# line_kick.net
KiCad netlist of a schematic drawn in EAGLE
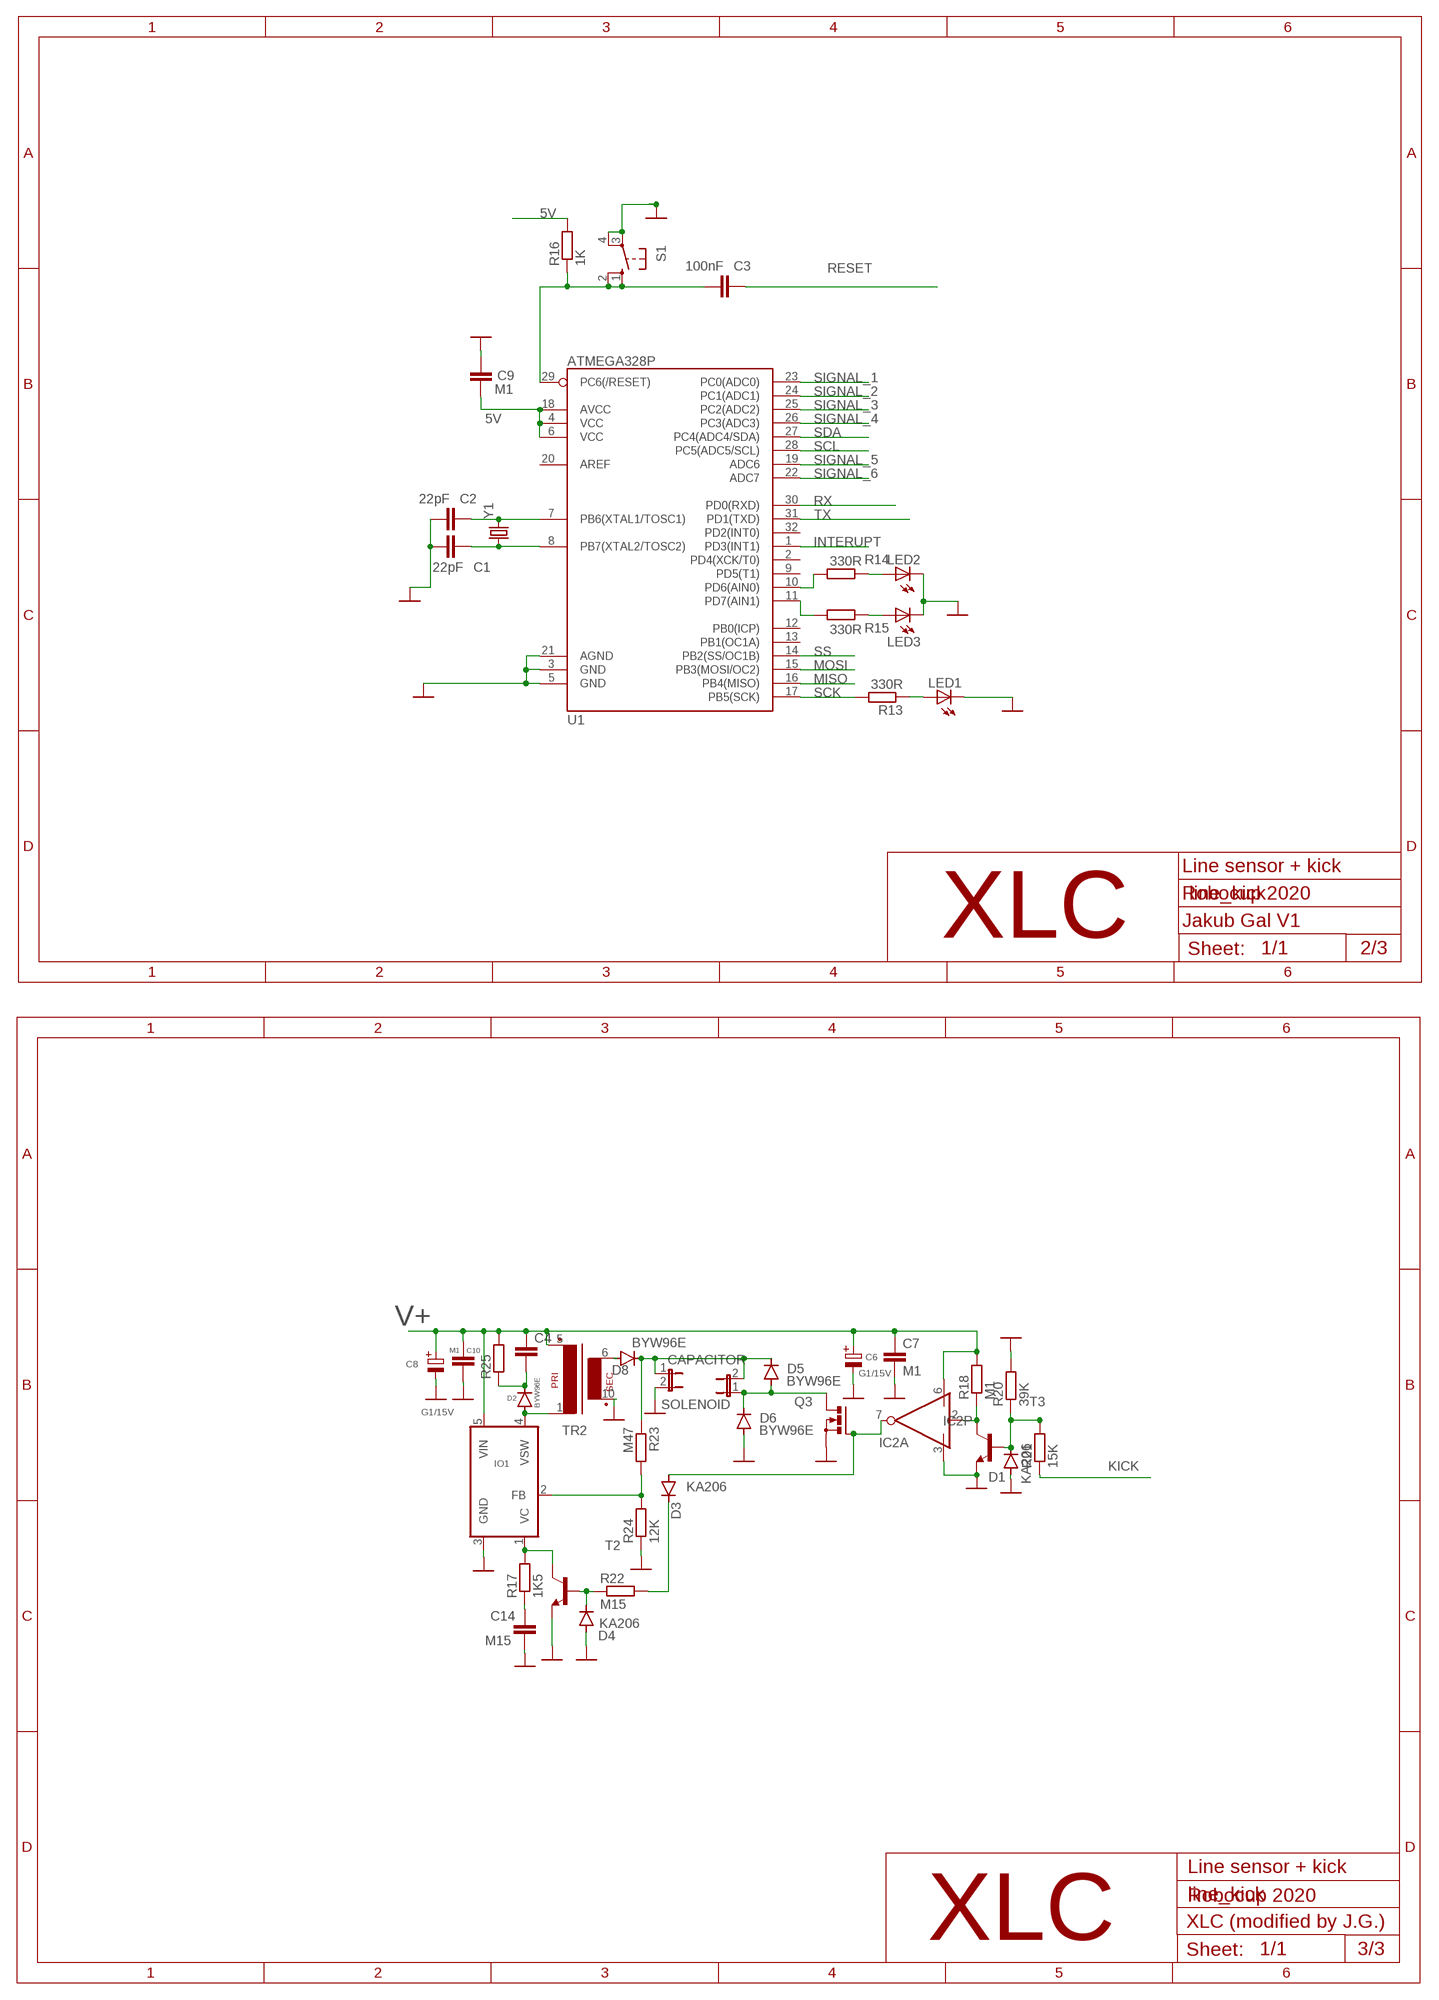
[diagram p0: schematic, sheet 1, part 1 of 2]
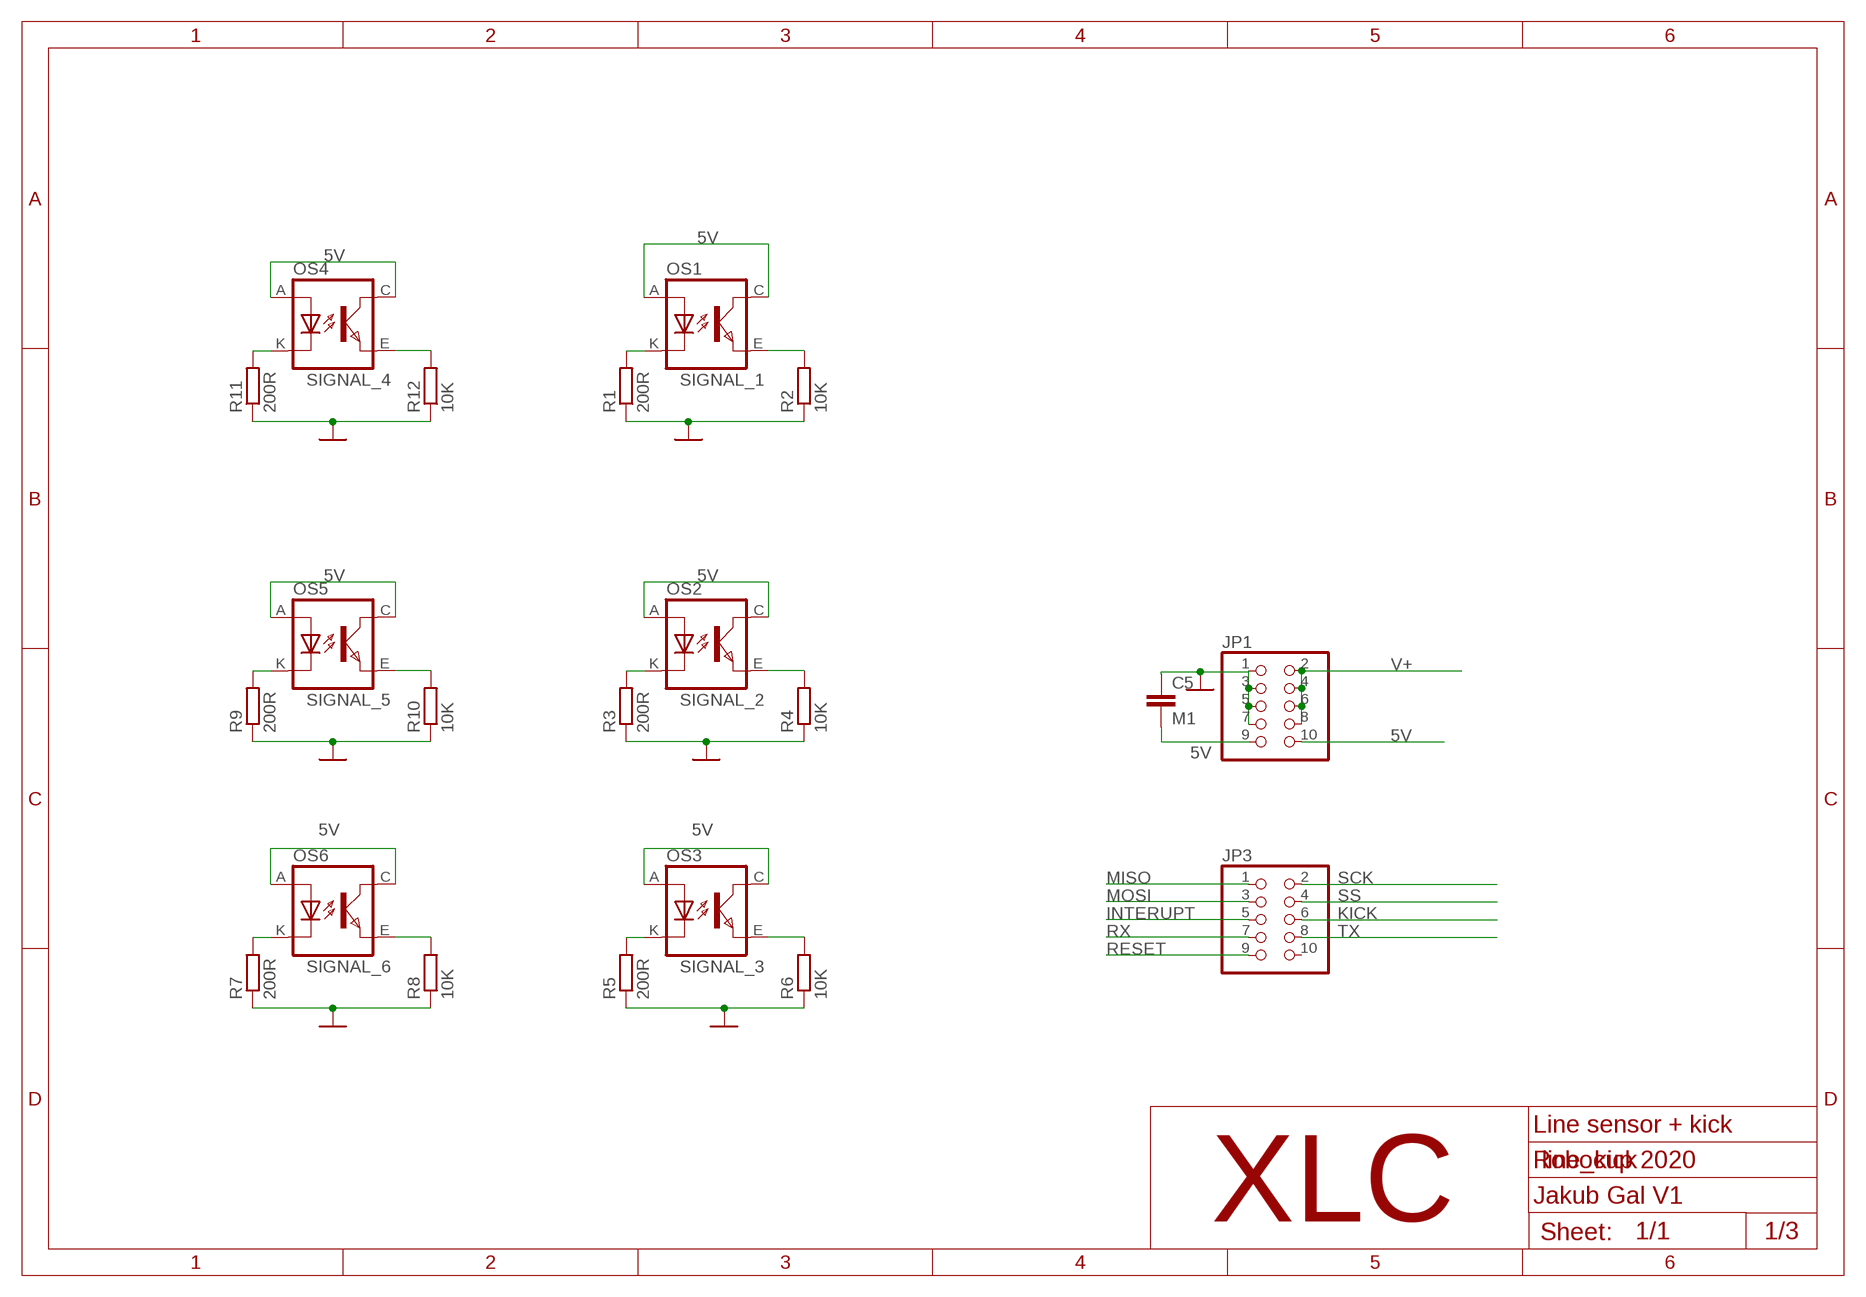
[diagram p1: schematic, sheet 1, part 2 of 2]

(export (version "E")
  (design (tool "Eeschema 10.0.6"))
  (components
    (comp (ref "C1")
      (value "22pF")
      (footprint "eagle-import:C0603")
      (libsource (lib "eagle-import") (part "C-EUC0603"))
    )
    (comp (ref "C2")
      (value "22pF")
      (footprint "eagle-import:C0603")
      (libsource (lib "eagle-import") (part "C-EUC0603"))
    )
    (comp (ref "C3")
      (value "100nF")
      (footprint "eagle-import:C0603")
      (libsource (lib "eagle-import") (part "C-EUC0603"))
    )
    (comp (ref "C4")
      (value "C-EU075-052X106")
      (footprint "eagle-import:C075-052X106")
      (libsource (lib "eagle-import") (part "rcl_334_C-EU075-052X106"))
    )
    (comp (ref "C5")
      (value "M1")
      (footprint "eagle-import:C0603")
      (libsource (lib "eagle-import") (part "rcl_334_C-EUC0603"))
    )
    (comp (ref "C6")
      (value "G1/15V")
      (footprint "eagle-import:E-2,5_7-RAD")
      (libsource (lib "eagle-import") (part "KOND-ELEKT-2,5/7"))
    )
    (comp (ref "C7")
      (value "M1")
      (footprint "eagle-import:C0805K")
      (libsource (lib "eagle-import") (part "resistor_348_C-EUC0805K"))
    )
    (comp (ref "C8")
      (value "G1/15V")
      (footprint "eagle-import:E-2,5_7-RAD")
      (libsource (lib "eagle-import") (part "KOND-ELEKT-2,5/7"))
    )
    (comp (ref "C9")
      (value "M1")
      (footprint "eagle-import:C0603")
      (libsource (lib "eagle-import") (part "C-EUC0603"))
    )
    (comp (ref "C10")
      (value "M1")
      (footprint "eagle-import:C0805K")
      (libsource (lib "eagle-import") (part "resistor_348_C-EUC0805K"))
    )
    (comp (ref "C14")
      (value "M15")
      (footprint "eagle-import:C1206")
      (libsource (lib "eagle-import") (part "resistor_348_C-EUC1206"))
    )
    (comp (ref "CAPACITOR")
      (value "JP1E")
      (footprint "eagle-import:JP1")
      (libsource (lib "eagle-import") (part "JP1E"))
    )
    (comp (ref "D1")
      (value "KA206")
      (footprint "eagle-import:D-7.5")
      (libsource (lib "eagle-import") (part "DIODE-D-7.5"))
    )
    (comp (ref "D2")
      (value "BYW96E")
      (footprint "eagle-import:SOD64-10")
      (libsource (lib "eagle-import") (part "BYW96"))
    )
    (comp (ref "D3")
      (value "KA206")
      (footprint "eagle-import:D-7.5")
      (libsource (lib "eagle-import") (part "DIODE-D-7.5"))
    )
    (comp (ref "D4")
      (value "KA206")
      (footprint "eagle-import:D-7.5")
      (libsource (lib "eagle-import") (part "DIODE-D-7.5"))
    )
    (comp (ref "D5")
      (value "BYW96E")
      (footprint "eagle-import:SOD64-10")
      (libsource (lib "eagle-import") (part "BYW96"))
    )
    (comp (ref "D6")
      (value "BYW96E")
      (footprint "eagle-import:SOD64-10")
      (libsource (lib "eagle-import") (part "BYW96"))
    )
    (comp (ref "D8")
      (value "BYW96E")
      (footprint "eagle-import:SOD64-10")
      (libsource (lib "eagle-import") (part "BYW96"))
    )
    (comp (ref "IC2")
      (value "MIC4423BM")
      (footprint "eagle-import:SO08")
      (libsource (lib "eagle-import") (part "MIC4423BM"))
    )
    (comp (ref "IO1")
      (value "LT1071V")
      (footprint "eagle-import:TO220-5P")
      (libsource (lib "eagle-import") (part "LT1071V"))
    )
    (comp (ref "JP1")
      (value "PINHD-2X5IDC")
      (footprint "eagle-import:2X05_IDC")
      (libsource (lib "eagle-import") (part "PINHD-2X5IDC"))
    )
    (comp (ref "JP3")
      (value "PINHD-2X5IDC")
      (footprint "eagle-import:2X05_IDC")
      (libsource (lib "eagle-import") (part "PINHD-2X5IDC"))
    )
    (comp (ref "LED1")
      (value "LEDCHIPLED_0603")
      (footprint "eagle-import:CHIPLED_0603")
      (libsource (lib "eagle-import") (part "LEDCHIPLED_0603"))
    )
    (comp (ref "LED2")
      (value "LEDCHIPLED_0603")
      (footprint "eagle-import:CHIPLED_0603")
      (libsource (lib "eagle-import") (part "LEDCHIPLED_0603"))
    )
    (comp (ref "LED3")
      (value "LEDCHIPLED_0603")
      (footprint "eagle-import:CHIPLED_0603")
      (libsource (lib "eagle-import") (part "LEDCHIPLED_0603"))
    )
    (comp (ref "OS1")
      (value "TCRT5000")
      (footprint "eagle-import:TCRT5000")
      (libsource (lib "eagle-import") (part "TCRT5000"))
    )
    (comp (ref "OS2")
      (value "TCRT5000")
      (footprint "eagle-import:TCRT5000")
      (libsource (lib "eagle-import") (part "TCRT5000"))
    )
    (comp (ref "OS3")
      (value "TCRT5000")
      (footprint "eagle-import:TCRT5000")
      (libsource (lib "eagle-import") (part "TCRT5000"))
    )
    (comp (ref "OS4")
      (value "TCRT5000")
      (footprint "eagle-import:TCRT5000")
      (fields (field (name "SPICEPREFIX") "O"))
      (libsource (lib "eagle-import") (part "TCRT5000"))
    )
    (comp (ref "OS5")
      (value "TCRT5000")
      (footprint "eagle-import:TCRT5000")
      (libsource (lib "eagle-import") (part "TCRT5000"))
    )
    (comp (ref "OS6")
      (value "TCRT5000")
      (footprint "eagle-import:TCRT5000")
      (fields (field (name "SPICEPREFIX") "O"))
      (libsource (lib "eagle-import") (part "TCRT5000"))
    )
    (comp (ref "Q3")
      (value "PMOSFET_NTO220BV")
      (footprint "eagle-import:TO220BV")
      (libsource (lib "eagle-import") (part "PMOSFET_NTO220BV"))
    )
    (comp (ref "R1")
      (value "200R")
      (footprint "eagle-import:R0603")
      (libsource (lib "eagle-import") (part "R-EU_R0603"))
    )
    (comp (ref "R2")
      (value "10K")
      (footprint "eagle-import:R0603")
      (libsource (lib "eagle-import") (part "R-EU_R0603"))
    )
    (comp (ref "R3")
      (value "200R")
      (footprint "eagle-import:R0603")
      (libsource (lib "eagle-import") (part "R-EU_R0603"))
    )
    (comp (ref "R4")
      (value "10K")
      (footprint "eagle-import:R0603")
      (libsource (lib "eagle-import") (part "R-EU_R0603"))
    )
    (comp (ref "R5")
      (value "200R")
      (footprint "eagle-import:R0603")
      (libsource (lib "eagle-import") (part "R-EU_R0603"))
    )
    (comp (ref "R6")
      (value "10K")
      (footprint "eagle-import:R0603")
      (libsource (lib "eagle-import") (part "R-EU_R0603"))
    )
    (comp (ref "R7")
      (value "200R")
      (footprint "eagle-import:R0603")
      (libsource (lib "eagle-import") (part "R-EU_R0603"))
    )
    (comp (ref "R8")
      (value "10K")
      (footprint "eagle-import:R0603")
      (libsource (lib "eagle-import") (part "R-EU_R0603"))
    )
    (comp (ref "R9")
      (value "200R")
      (footprint "eagle-import:R0603")
      (libsource (lib "eagle-import") (part "R-EU_R0603"))
    )
    (comp (ref "R10")
      (value "10K")
      (footprint "eagle-import:R0603")
      (libsource (lib "eagle-import") (part "R-EU_R0603"))
    )
    (comp (ref "R11")
      (value "200R")
      (footprint "eagle-import:R0603")
      (libsource (lib "eagle-import") (part "R-EU_R0603"))
    )
    (comp (ref "R12")
      (value "10K")
      (footprint "eagle-import:R0603")
      (libsource (lib "eagle-import") (part "R-EU_R0603"))
    )
    (comp (ref "R13")
      (value "330R")
      (footprint "eagle-import:R0603")
      (libsource (lib "eagle-import") (part "R-EU_R0603"))
    )
    (comp (ref "R14")
      (value "330R")
      (footprint "eagle-import:R0603")
      (libsource (lib "eagle-import") (part "R-EU_R0603"))
    )
    (comp (ref "R15")
      (value "330R")
      (footprint "eagle-import:R0603")
      (libsource (lib "eagle-import") (part "R-EU_R0603"))
    )
    (comp (ref "R16")
      (value "1K")
      (footprint "eagle-import:R0603")
      (libsource (lib "eagle-import") (part "R-EU_R0603"))
    )
    (comp (ref "R17")
      (value "1K5")
      (footprint "eagle-import:R1206")
      (libsource (lib "eagle-import") (part "R-EU_R1206"))
    )
    (comp (ref "R18")
      (value "M1")
      (footprint "eagle-import:R1206")
      (libsource (lib "eagle-import") (part "R-EU_R1206"))
    )
    (comp (ref "R20")
      (value "39K")
      (footprint "eagle-import:R1206")
      (libsource (lib "eagle-import") (part "R-EU_R1206"))
    )
    (comp (ref "R21")
      (value "15K")
      (footprint "eagle-import:R1206")
      (libsource (lib "eagle-import") (part "R-EU_R1206"))
    )
    (comp (ref "R22")
      (value "M15")
      (footprint "eagle-import:R1206")
      (libsource (lib "eagle-import") (part "R-EU_R1206"))
    )
    (comp (ref "R23")
      (value "M47")
      (footprint "eagle-import:R1206")
      (libsource (lib "eagle-import") (part "R-EU_R1206"))
    )
    (comp (ref "R24")
      (value "12K")
      (footprint "eagle-import:R1206")
      (libsource (lib "eagle-import") (part "R-EU_R1206"))
    )
    (comp (ref "R25")
      (value "REZISTOR-7,5MM-HORIZ")
      (footprint "eagle-import:R-7,5H")
      (libsource (lib "eagle-import") (part "REZISTOR-7,5MM-HORIZ"))
    )
    (comp (ref "S1")
      (value "10-XX")
      (footprint "eagle-import:B3F-10XX")
      (fields (field (name "MPN") "B3F-1000"))
      (libsource (lib "eagle-import") (part "10-XX"))
    )
    (comp (ref "SOLENOID")
      (value "JP1E")
      (footprint "eagle-import:JP1")
      (libsource (lib "eagle-import") (part "JP1E"))
    )
    (comp (ref "T2")
      (value "-NPN-SC59-BEC")
      (footprint "eagle-import:SC59-BEC")
      (libsource (lib "eagle-import") (part "-NPN-SC59-BEC"))
    )
    (comp (ref "T3")
      (value "-NPN-SC59-BEC")
      (footprint "eagle-import:SC59-BEC")
      (libsource (lib "eagle-import") (part "-NPN-SC59-BEC"))
    )
    (comp (ref "TR2")
      (value "TRAFO-E10-R\"\"")
      (footprint "eagle-import:TRAFO-EE17X20")
      (libsource (lib "eagle-import") (part "TRAFO-E10-R{dblquote}{dblquote}"))
    )
    (comp (ref "U1")
      (value "ATMEGA328P")
      (footprint "eagle-import:TQFP32-08")
      (libsource (lib "eagle-import") (part "ATMEGA328_SMT"))
    )
    (comp (ref "Y1")
      (value "CRYSTALHC49US")
      (footprint "eagle-import:HC49US")
      (libsource (lib "eagle-import") (part "CRYSTALHC49US"))
    )
  )
  (nets
    (net (code "1") (name "/5V") (class "Default")
      (node (ref "C5") (pin "2") (pinfunction "2_2") (pintype "passive"))
      (node (ref "C9") (pin "1") (pinfunction "1_1") (pintype "passive"))
      (node (ref "JP1") (pin "10") (pinfunction "10_10") (pintype "passive"))
      (node (ref "JP1") (pin "9") (pinfunction "9_9") (pintype "passive"))
      (node (ref "OS1") (pin "A") (pinfunction "ANODE_A") (pintype "passive"))
      (node (ref "OS1") (pin "C") (pinfunction "COLLECTOR_C") (pintype "passive"))
      (node (ref "OS2") (pin "A") (pinfunction "ANODE_A") (pintype "passive"))
      (node (ref "OS2") (pin "C") (pinfunction "COLLECTOR_C") (pintype "passive"))
      (node (ref "OS3") (pin "A") (pinfunction "ANODE_A") (pintype "passive"))
      (node (ref "OS3") (pin "C") (pinfunction "COLLECTOR_C") (pintype "passive"))
      (node (ref "OS4") (pin "A") (pinfunction "ANODE_A") (pintype "passive"))
      (node (ref "OS4") (pin "C") (pinfunction "COLLECTOR_C") (pintype "passive"))
      (node (ref "OS5") (pin "A") (pinfunction "ANODE_A") (pintype "passive"))
      (node (ref "OS5") (pin "C") (pinfunction "COLLECTOR_C") (pintype "passive"))
      (node (ref "OS6") (pin "A") (pinfunction "ANODE_A") (pintype "passive"))
      (node (ref "OS6") (pin "C") (pinfunction "COLLECTOR_C") (pintype "passive"))
      (node (ref "R16") (pin "2") (pinfunction "2_2") (pintype "passive"))
      (node (ref "U1") (pin "18") (pinfunction "AVCC_18") (pintype "bidirectional"))
      (node (ref "U1") (pin "4") (pinfunction "VCC_4") (pintype "bidirectional"))
      (node (ref "U1") (pin "6") (pinfunction "VCC_6") (pintype "bidirectional"))
    )
    (net (code "2") (name "/INTERUPT") (class "Default")
      (node (ref "JP3") (pin "5") (pinfunction "5_5") (pintype "passive"))
      (node (ref "U1") (pin "1") (pinfunction "PD3(INT1)_1") (pintype "bidirectional"))
    )
    (net (code "3") (name "/KICK") (class "Default")
      (node (ref "JP3") (pin "6") (pinfunction "6_6") (pintype "passive"))
      (node (ref "R21") (pin "1") (pinfunction "1_1") (pintype "passive"))
    )
    (net (code "4") (name "/MISO") (class "Default")
      (node (ref "JP3") (pin "1") (pinfunction "1_1") (pintype "passive"))
      (node (ref "U1") (pin "16") (pinfunction "PB4(MISO)_16") (pintype "bidirectional"))
    )
    (net (code "5") (name "/MOSI") (class "Default")
      (node (ref "JP3") (pin "3") (pinfunction "3_3") (pintype "passive"))
      (node (ref "U1") (pin "15") (pinfunction "PB3(MOSI/OC2)_15") (pintype "bidirectional"))
    )
    (net (code "6") (name "/RESET") (class "Default")
      (node (ref "C3") (pin "2") (pinfunction "2_2") (pintype "passive"))
      (node (ref "JP3") (pin "9") (pinfunction "9_9") (pintype "passive"))
    )
    (net (code "7") (name "/RX") (class "Default")
      (node (ref "JP3") (pin "7") (pinfunction "7_7") (pintype "passive"))
      (node (ref "U1") (pin "30") (pinfunction "PD0(RXD)_30") (pintype "bidirectional"))
    )
    (net (code "8") (name "/SCK") (class "Default")
      (node (ref "JP3") (pin "2") (pinfunction "2_2") (pintype "passive"))
      (node (ref "R13") (pin "2") (pinfunction "2_2") (pintype "passive"))
      (node (ref "U1") (pin "17") (pinfunction "PB5(SCK)_17") (pintype "bidirectional"))
    )
    (net (code "9") (name "/SCL") (class "Default")
      (node (ref "U1") (pin "28") (pinfunction "PC5(ADC5/SCL)_28") (pintype "bidirectional"))
    )
    (net (code "10") (name "/SDA") (class "Default")
      (node (ref "U1") (pin "27") (pinfunction "PC4(ADC4/SDA)_27") (pintype "bidirectional"))
    )
    (net (code "11") (name "/SIGNAL_1") (class "Default")
      (node (ref "OS1") (pin "E") (pinfunction "EMITTER_E") (pintype "passive"))
      (node (ref "R2") (pin "2") (pinfunction "2_2") (pintype "passive"))
      (node (ref "U1") (pin "23") (pinfunction "PC0(ADC0)_23") (pintype "bidirectional"))
    )
    (net (code "12") (name "/SIGNAL_2") (class "Default")
      (node (ref "OS2") (pin "E") (pinfunction "EMITTER_E") (pintype "passive"))
      (node (ref "R4") (pin "2") (pinfunction "2_2") (pintype "passive"))
      (node (ref "U1") (pin "24") (pinfunction "PC1(ADC1)_24") (pintype "bidirectional"))
    )
    (net (code "13") (name "/SIGNAL_3") (class "Default")
      (node (ref "OS3") (pin "E") (pinfunction "EMITTER_E") (pintype "passive"))
      (node (ref "R6") (pin "2") (pinfunction "2_2") (pintype "passive"))
      (node (ref "U1") (pin "25") (pinfunction "PC2(ADC2)_25") (pintype "bidirectional"))
    )
    (net (code "14") (name "/SIGNAL_4") (class "Default")
      (node (ref "OS4") (pin "E") (pinfunction "EMITTER_E") (pintype "passive"))
      (node (ref "R12") (pin "2") (pinfunction "2_2") (pintype "passive"))
      (node (ref "U1") (pin "26") (pinfunction "PC3(ADC3)_26") (pintype "bidirectional"))
    )
    (net (code "15") (name "/SIGNAL_5") (class "Default")
      (node (ref "OS5") (pin "E") (pinfunction "EMITTER_E") (pintype "passive"))
      (node (ref "R10") (pin "2") (pinfunction "2_2") (pintype "passive"))
      (node (ref "U1") (pin "19") (pinfunction "ADC6_19") (pintype "bidirectional"))
    )
    (net (code "16") (name "/SIGNAL_6") (class "Default")
      (node (ref "OS6") (pin "E") (pinfunction "EMITTER_E") (pintype "passive"))
      (node (ref "R8") (pin "2") (pinfunction "2_2") (pintype "passive"))
      (node (ref "U1") (pin "22") (pinfunction "ADC7_22") (pintype "bidirectional"))
    )
    (net (code "17") (name "/SS") (class "Default")
      (node (ref "JP3") (pin "4") (pinfunction "4_4") (pintype "passive"))
      (node (ref "U1") (pin "14") (pinfunction "PB2(SS/OC1B)_14") (pintype "bidirectional"))
    )
    (net (code "18") (name "/TX") (class "Default")
      (node (ref "JP3") (pin "8") (pinfunction "8_8") (pintype "passive"))
      (node (ref "U1") (pin "31") (pinfunction "PD1(TXD)_31") (pintype "bidirectional"))
    )
    (net (code "19") (name "/V+") (class "Default")
      (node (ref "C10") (pin "1") (pinfunction "1_1") (pintype "passive"))
      (node (ref "C4") (pin "1") (pinfunction "1_1") (pintype "passive"))
      (node (ref "C6") (pin "+") (pinfunction "+_+") (pintype "passive"))
      (node (ref "C7") (pin "1") (pinfunction "1_1") (pintype "passive"))
      (node (ref "C8") (pin "+") (pinfunction "+_+") (pintype "passive"))
      (node (ref "IC2") (pin "6") (pinfunction "V+_6") (pintype "power_in"))
      (node (ref "IO1") (pin "5") (pinfunction "VIN_5") (pintype "power_in"))
      (node (ref "JP1") (pin "2") (pinfunction "2_2") (pintype "passive"))
      (node (ref "JP1") (pin "4") (pinfunction "4_4") (pintype "passive"))
      (node (ref "JP1") (pin "6") (pinfunction "6_6") (pintype "passive"))
      (node (ref "JP1") (pin "8") (pinfunction "8_8") (pintype "passive"))
      (node (ref "R18") (pin "2") (pinfunction "2_2") (pintype "passive"))
      (node (ref "R25") (pin "2") (pinfunction "2_2") (pintype "passive"))
      (node (ref "TR2") (pin "5") (pinfunction "2_5") (pintype "passive"))
    )
    (net (code "20") (name "GND") (class "Default")
      (node (ref "C1") (pin "1") (pinfunction "1_1") (pintype "passive"))
      (node (ref "C10") (pin "2") (pinfunction "2_2") (pintype "passive"))
      (node (ref "C14") (pin "2") (pinfunction "2_2") (pintype "passive"))
      (node (ref "C2") (pin "1") (pinfunction "1_1") (pintype "passive"))
      (node (ref "C5") (pin "1") (pinfunction "1_1") (pintype "passive"))
      (node (ref "C6") (pin "-") (pinfunction "-_-") (pintype "passive"))
      (node (ref "C7") (pin "2") (pinfunction "2_2") (pintype "passive"))
      (node (ref "C8") (pin "-") (pinfunction "-_-") (pintype "passive"))
      (node (ref "C9") (pin "2") (pinfunction "2_2") (pintype "passive"))
      (node (ref "CAPACITOR") (pin "2") (pinfunction "2_2") (pintype "passive"))
      (node (ref "D1") (pin "A") (pinfunction "A_A") (pintype "passive"))
      (node (ref "D4") (pin "A") (pinfunction "A_A") (pintype "passive"))
      (node (ref "D6") (pin "A") (pinfunction "A_A") (pintype "passive"))
      (node (ref "IC2") (pin "3") (pinfunction "GND_3") (pintype "power_in"))
      (node (ref "IO1") (pin "3") (pinfunction "GND_3") (pintype "power_in"))
      (node (ref "JP1") (pin "1") (pinfunction "1_1") (pintype "passive"))
      (node (ref "JP1") (pin "3") (pinfunction "3_3") (pintype "passive"))
      (node (ref "JP1") (pin "5") (pinfunction "5_5") (pintype "passive"))
      (node (ref "JP1") (pin "7") (pinfunction "7_7") (pintype "passive"))
      (node (ref "LED1") (pin "C") (pinfunction "C_C") (pintype "passive"))
      (node (ref "LED2") (pin "C") (pinfunction "C_C") (pintype "passive"))
      (node (ref "LED3") (pin "C") (pinfunction "C_C") (pintype "passive"))
      (node (ref "Q3") (pin "S") (pinfunction "S_S") (pintype "passive"))
      (node (ref "R1") (pin "1") (pinfunction "1_1") (pintype "passive"))
      (node (ref "R10") (pin "1") (pinfunction "1_1") (pintype "passive"))
      (node (ref "R11") (pin "1") (pinfunction "1_1") (pintype "passive"))
      (node (ref "R12") (pin "1") (pinfunction "1_1") (pintype "passive"))
      (node (ref "R2") (pin "1") (pinfunction "1_1") (pintype "passive"))
      (node (ref "R20") (pin "2") (pinfunction "2_2") (pintype "passive"))
      (node (ref "R24") (pin "1") (pinfunction "1_1") (pintype "passive"))
      (node (ref "R3") (pin "1") (pinfunction "1_1") (pintype "passive"))
      (node (ref "R4") (pin "1") (pinfunction "1_1") (pintype "passive"))
      (node (ref "R5") (pin "1") (pinfunction "1_1") (pintype "passive"))
      (node (ref "R6") (pin "1") (pinfunction "1_1") (pintype "passive"))
      (node (ref "R7") (pin "1") (pinfunction "1_1") (pintype "passive"))
      (node (ref "R8") (pin "1") (pinfunction "1_1") (pintype "passive"))
      (node (ref "R9") (pin "1") (pinfunction "1_1") (pintype "passive"))
      (node (ref "S1") (pin "3") (pinfunction "P_3") (pintype "passive"))
      (node (ref "S1") (pin "4") (pinfunction "P1_4") (pintype "passive"))
      (node (ref "T2") (pin "E") (pinfunction "E_E") (pintype "passive"))
      (node (ref "T3") (pin "E") (pinfunction "E_E") (pintype "passive"))
      (node (ref "TR2") (pin "10") (pinfunction "4_10") (pintype "passive"))
      (node (ref "U1") (pin "21") (pinfunction "AGND_21") (pintype "bidirectional"))
      (node (ref "U1") (pin "3") (pinfunction "GND_3") (pintype "bidirectional"))
      (node (ref "U1") (pin "5") (pinfunction "GND_5") (pintype "bidirectional"))
    )
    (net (code "21") (name "Net-(C4-Pad2)") (class "Default")
      (node (ref "C4") (pin "2") (pinfunction "2_2") (pintype "passive"))
      (node (ref "D2") (pin "C") (pinfunction "C_C") (pintype "passive"))
      (node (ref "R25") (pin "1") (pinfunction "1_1") (pintype "passive"))
    )
    (net (code "22") (name "Net-(C14-Pad1)") (class "Default")
      (node (ref "C14") (pin "1") (pinfunction "1_1") (pintype "passive"))
      (node (ref "R17") (pin "1") (pinfunction "1_1") (pintype "passive"))
    )
    (net (code "23") (name "Net-(CAPACITOR-Pad1)") (class "Default")
      (node (ref "CAPACITOR") (pin "1") (pinfunction "1_1") (pintype "passive"))
      (node (ref "D5") (pin "C") (pinfunction "C_C") (pintype "passive"))
      (node (ref "D8") (pin "C") (pinfunction "C_C") (pintype "passive"))
      (node (ref "R23") (pin "1") (pinfunction "1_1") (pintype "passive"))
      (node (ref "SOLENOID") (pin "2") (pinfunction "2_2") (pintype "passive"))
    )
    (net (code "24") (name "Net-(D1-PadC)") (class "Default")
      (node (ref "D1") (pin "C") (pinfunction "C_C") (pintype "passive"))
      (node (ref "R20") (pin "1") (pinfunction "1_1") (pintype "passive"))
      (node (ref "R21") (pin "2") (pinfunction "2_2") (pintype "passive"))
      (node (ref "T3") (pin "B") (pinfunction "B_B") (pintype "passive"))
    )
    (net (code "25") (name "Net-(D3-PadC)") (class "Default")
      (node (ref "D3") (pin "C") (pinfunction "C_C") (pintype "passive"))
      (node (ref "R22") (pin "2") (pinfunction "2_2") (pintype "passive"))
    )
    (net (code "26") (name "Net-(D4-PadC)") (class "Default")
      (node (ref "D4") (pin "C") (pinfunction "C_C") (pintype "passive"))
      (node (ref "R22") (pin "1") (pinfunction "1_1") (pintype "passive"))
      (node (ref "T2") (pin "B") (pinfunction "B_B") (pintype "passive"))
    )
    (net (code "27") (name "Net-(D5-PadA)") (class "Default")
      (node (ref "D5") (pin "A") (pinfunction "A_A") (pintype "passive"))
      (node (ref "D6") (pin "C") (pinfunction "C_C") (pintype "passive"))
      (node (ref "Q3") (pin "D") (pinfunction "D_D") (pintype "passive"))
      (node (ref "SOLENOID") (pin "1") (pinfunction "1_1") (pintype "passive"))
    )
    (net (code "28") (name "Net-(IC2A-IN)") (class "Default")
      (node (ref "IC2") (pin "2") (pinfunction "IN_2") (pintype "input"))
      (node (ref "R18") (pin "1") (pinfunction "1_1") (pintype "passive"))
      (node (ref "T3") (pin "C") (pinfunction "C_C") (pintype "passive"))
    )
    (net (code "29") (name "Net-(IC2A-OUT)") (class "Default")
      (node (ref "D3") (pin "A") (pinfunction "A_A") (pintype "passive"))
      (node (ref "IC2") (pin "7") (pinfunction "OUT_7") (pintype "output"))
      (node (ref "Q3") (pin "G") (pinfunction "G_G") (pintype "passive"))
    )
    (net (code "30") (name "Net-(IO1-FB)") (class "Default")
      (node (ref "IO1") (pin "2") (pinfunction "FB_2") (pintype "input"))
      (node (ref "R23") (pin "2") (pinfunction "2_2") (pintype "passive"))
      (node (ref "R24") (pin "2") (pinfunction "2_2") (pintype "passive"))
    )
    (net (code "31") (name "Net-(IO1-VC)") (class "Default")
      (node (ref "IO1") (pin "1") (pinfunction "VC_1") (pintype "input"))
      (node (ref "R17") (pin "2") (pinfunction "2_2") (pintype "passive"))
      (node (ref "T2") (pin "C") (pinfunction "C_C") (pintype "passive"))
    )
    (net (code "32") (name "Net-(IO1-VSW)") (class "Default")
      (node (ref "D2") (pin "A") (pinfunction "A_A") (pintype "passive"))
      (node (ref "IO1") (pin "4") (pinfunction "VSW_4") (pintype "output"))
      (node (ref "TR2") (pin "1") (pinfunction "1_1") (pintype "passive"))
    )
    (net (code "33") (name "Net-(LED1-PadA)") (class "Default")
      (node (ref "LED1") (pin "A") (pinfunction "A_A") (pintype "passive"))
      (node (ref "R13") (pin "1") (pinfunction "1_1") (pintype "passive"))
    )
    (net (code "34") (name "Net-(LED2-PadA)") (class "Default")
      (node (ref "LED2") (pin "A") (pinfunction "A_A") (pintype "passive"))
      (node (ref "R14") (pin "1") (pinfunction "1_1") (pintype "passive"))
    )
    (net (code "35") (name "Net-(LED3-PadA)") (class "Default")
      (node (ref "LED3") (pin "A") (pinfunction "A_A") (pintype "passive"))
      (node (ref "R15") (pin "1") (pinfunction "1_1") (pintype "passive"))
    )
    (net (code "36") (name "Net-(OS1-CATHODE)") (class "Default")
      (node (ref "OS1") (pin "K") (pinfunction "CATHODE_K") (pintype "passive"))
      (node (ref "R1") (pin "2") (pinfunction "2_2") (pintype "passive"))
    )
    (net (code "37") (name "Net-(OS2-CATHODE)") (class "Default")
      (node (ref "OS2") (pin "K") (pinfunction "CATHODE_K") (pintype "passive"))
      (node (ref "R3") (pin "2") (pinfunction "2_2") (pintype "passive"))
    )
    (net (code "38") (name "Net-(OS3-CATHODE)") (class "Default")
      (node (ref "OS3") (pin "K") (pinfunction "CATHODE_K") (pintype "passive"))
      (node (ref "R5") (pin "2") (pinfunction "2_2") (pintype "passive"))
    )
    (net (code "39") (name "Net-(OS4-CATHODE)") (class "Default")
      (node (ref "OS4") (pin "K") (pinfunction "CATHODE_K") (pintype "passive"))
      (node (ref "R11") (pin "2") (pinfunction "2_2") (pintype "passive"))
    )
    (net (code "40") (name "Net-(OS5-CATHODE)") (class "Default")
      (node (ref "OS5") (pin "K") (pinfunction "CATHODE_K") (pintype "passive"))
      (node (ref "R9") (pin "2") (pinfunction "2_2") (pintype "passive"))
    )
    (net (code "41") (name "Net-(OS6-CATHODE)") (class "Default")
      (node (ref "OS6") (pin "K") (pinfunction "CATHODE_K") (pintype "passive"))
      (node (ref "R7") (pin "2") (pinfunction "2_2") (pintype "passive"))
    )
    (net (code "42") (name "Net-(S1-S)") (class "Default")
      (node (ref "C3") (pin "1") (pinfunction "1_1") (pintype "passive"))
      (node (ref "R16") (pin "1") (pinfunction "1_1") (pintype "passive"))
      (node (ref "S1") (pin "1") (pinfunction "S_1") (pintype "passive"))
      (node (ref "S1") (pin "2") (pinfunction "S1_2") (pintype "passive"))
      (node (ref "U1") (pin "29") (pinfunction "PC6(/RESET)_29") (pintype "bidirectional"))
    )
    (net (code "43") (name "Net-(TR2-3)") (class "Default")
      (node (ref "D8") (pin "A") (pinfunction "A_A") (pintype "passive"))
      (node (ref "TR2") (pin "6") (pinfunction "3_6") (pintype "passive"))
    )
    (net (code "44") (name "Net-(U1-PB6(XTAL1{slash}TOSC1))") (class "Default")
      (node (ref "C2") (pin "2") (pinfunction "2_2") (pintype "passive"))
      (node (ref "U1") (pin "7") (pinfunction "PB6(XTAL1/TOSC1)_7") (pintype "bidirectional"))
      (node (ref "Y1") (pin "2") (pinfunction "2_2") (pintype "passive"))
    )
    (net (code "45") (name "Net-(U1-PB7(XTAL2{slash}TOSC2))") (class "Default")
      (node (ref "C1") (pin "2") (pinfunction "2_2") (pintype "passive"))
      (node (ref "U1") (pin "8") (pinfunction "PB7(XTAL2/TOSC2)_8") (pintype "bidirectional"))
      (node (ref "Y1") (pin "1") (pinfunction "1_1") (pintype "passive"))
    )
    (net (code "46") (name "Net-(U1-PD6(AIN0))") (class "Default")
      (node (ref "R14") (pin "2") (pinfunction "2_2") (pintype "passive"))
      (node (ref "U1") (pin "10") (pinfunction "PD6(AIN0)_10") (pintype "bidirectional"))
    )
    (net (code "47") (name "Net-(U1-PD7(AIN1))") (class "Default")
      (node (ref "R15") (pin "2") (pinfunction "2_2") (pintype "passive"))
      (node (ref "U1") (pin "11") (pinfunction "PD7(AIN1)_11") (pintype "bidirectional"))
    )
    (net (code "48") (name "unconnected-(JP3-Pad10)") (class "Default")
      (node (ref "JP3") (pin "10") (pinfunction "10_10") (pintype "passive"))
    )
    (net (code "49") (name "unconnected-(U1-AREF-Pad20)") (class "Default")
      (node (ref "U1") (pin "20") (pinfunction "AREF_20") (pintype "bidirectional"))
    )
    (net (code "50") (name "unconnected-(U1-PB0(ICP)-Pad12)") (class "Default")
      (node (ref "U1") (pin "12") (pinfunction "PB0(ICP)_12") (pintype "bidirectional"))
    )
    (net (code "51") (name "unconnected-(U1-PB1(OC1A)-Pad13)") (class "Default")
      (node (ref "U1") (pin "13") (pinfunction "PB1(OC1A)_13") (pintype "bidirectional"))
    )
    (net (code "52") (name "unconnected-(U1-PD2(INT0)-Pad32)") (class "Default")
      (node (ref "U1") (pin "32") (pinfunction "PD2(INT0)_32") (pintype "bidirectional"))
    )
    (net (code "53") (name "unconnected-(U1-PD4(XCK{slash}T0)-Pad2)") (class "Default")
      (node (ref "U1") (pin "2") (pinfunction "PD4(XCK/T0)_2") (pintype "bidirectional"))
    )
    (net (code "54") (name "unconnected-(U1-PD5(T1)-Pad9)") (class "Default")
      (node (ref "U1") (pin "9") (pinfunction "PD5(T1)_9") (pintype "bidirectional"))
    )
  )
)
